# Controllers.net
KiCad netlist of a schematic drawn in Altium Designer
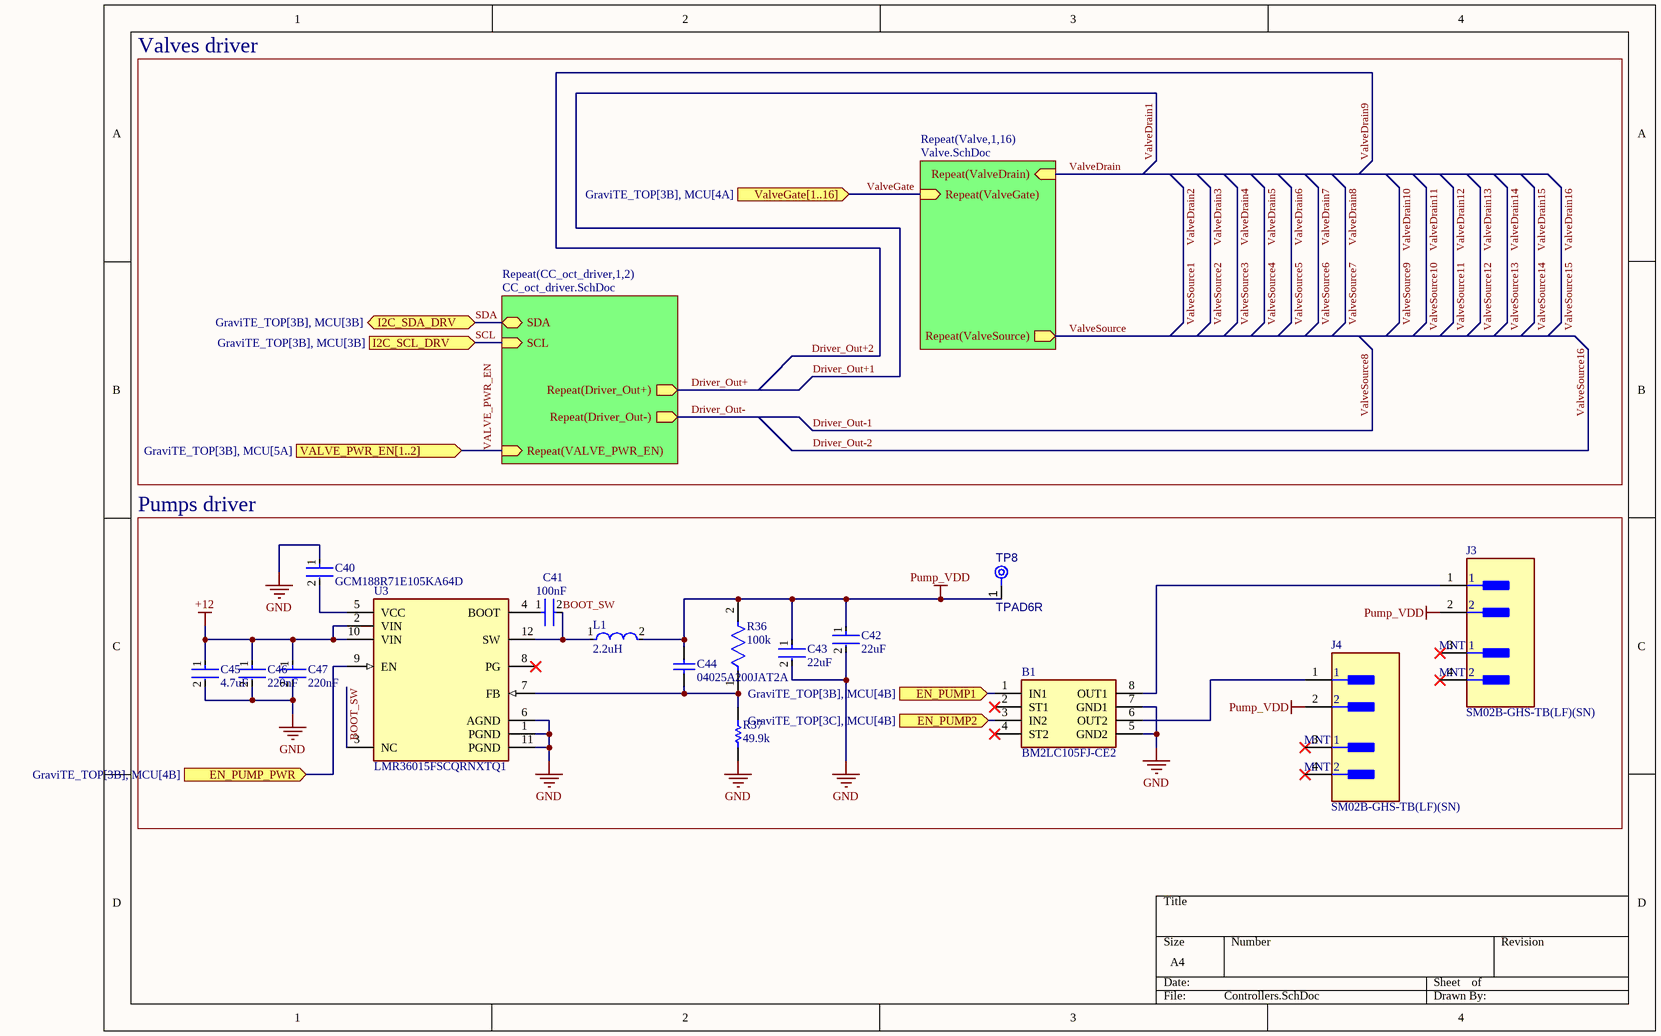
[diagram p0: Controllers.SchDoc]

(export (version "E")
  (design (tool "Eeschema 10.0.6"))
  (components
    (comp (ref "B1")
      (value "BM2LC105FJ-CE2")
      (footprint "SOIC127P600X165-8N")
      (description "Smart Low Side Switch ICs")
      (fields (field (name "MOUSER PART NUMBER") "755-BM2LC105FJ-CE2"))
      (libsource (lib "BM2LC105FJ-CE2") (part "BM2LC105FJ-CE2"))
    )
    (comp (ref "C40")
      (value "GCM188R71E105KA64D")
      (footprint "FP-GCM188-0_1-MFG")
      (fields (field (name "TOLERANCE") "10%") (field (name "VOLTAGE") "25V"))
      (libsource (lib "Altium Content Vault") (part "02cd4be3c70576c341d710602a673aa"))
    )
    (comp (ref "C41")
      (value "100nF")
      (footprint "FP-GCM155-0_05-IPC_C")
      (description "Ceramic Capacitor for Automotive 100nF ±10% 16VDC X7R 0402 Paper T/R")
      (fields (field (name "VOLTAGE") "16V") (field (name "TOLERANCE") "10%"))
      (libsource (lib "Altium Content Vault") (part "02cd4be3c70576c341d710602a673aa"))
    )
    (comp (ref "C42")
      (value "22uF")
      (footprint "FP-CGA5L-0_3-0_1-IPC_A")
      (description "Cap Ceramic 22uF 16V X5R 20% Pad SMD 1206 +85°C Automotive T/R")
      (fields (field (name "TOLERANCE") "20%"))
      (libsource (lib "Altium Content Vault") (part "b4654b650e69147ec39a6b967a45e02"))
    )
    (comp (ref "C43")
      (value "22uF")
      (footprint "FP-CGA5L-0_3-0_1-IPC_A")
      (description "Cap Ceramic 22uF 16V X5R 20% Pad SMD 1206 +85°C Automotive T/R")
      (fields (field (name "TOLERANCE") "20%"))
      (libsource (lib "Altium Content Vault") (part "b4654b650e69147ec39a6b967a45e02"))
    )
    (comp (ref "C44")
      (value "04025A200JAT2A")
      (footprint "CAPC1005X56X25NL10T15")
      (fields (field (name "MANUFACTURER") "AVX Interconnect / Elco"))
      (libsource (lib "Altium Content Vault") (part "CAP"))
    )
    (comp (ref "C45")
      (value "4.7uF")
      (footprint "FP-GCM21B-0_2-e0_2_0_7-IPC_B")
      (description "Ceramic Capacitor for Automotive 4.7uF ±10% 25VDC X7S 0805 Embossed T/R")
      (libsource (lib "Altium Content Vault") (part "11868f565c42a9108669ba33697ecf6"))
    )
    (comp (ref "C46")
      (value "220nF")
      (footprint "FP-GCM188-0_1-IPC_B")
      (description "Ceramic Capacitor for Automotive 220nF  ±10% 25VDC X7R 0603 Paper T/R")
      (fields (field (name "VOLTAGE") "25V") (field (name "TOLERANCE") "10%"))
      (libsource (lib "Altium Content Vault") (part "02cd4be3c70576c341d710602a673aa"))
    )
    (comp (ref "C47")
      (value "220nF")
      (footprint "FP-GCM188-0_1-IPC_B")
      (description "Ceramic Capacitor for Automotive 220nF  ±10% 25VDC X7R 0603 Paper T/R")
      (fields (field (name "VOLTAGE") "25V") (field (name "TOLERANCE") "10%"))
      (libsource (lib "Altium Content Vault") (part "02cd4be3c70576c341d710602a673aa"))
    )
    (comp (ref "J3")
      (value "SM02B-GHS-TB(LF)(SN)")
      (footprint "FP-SM02B-GHS-TB_LF_SN-MFG")
      (description "CONN HEADER SMD R/A 2POS 1.25MM")
      (libsource (lib "Altium Content Vault") (part "56ec3178a87b3978bdc1b3682cd516a"))
    )
    (comp (ref "J4")
      (value "SM02B-GHS-TB(LF)(SN)")
      (footprint "FP-SM02B-GHS-TB_LF_SN-MFG")
      (description "CONN HEADER SMD R/A 2POS 1.25MM")
      (libsource (lib "Altium Content Vault") (part "56ec3178a87b3978bdc1b3682cd516a"))
    )
    (comp (ref "L1")
      (value "2.2uH")
      (footprint "FP-MLP2520S-MFG")
      (description "Shielded Multilayer Inductor 2.2uH ±20% 1200mA 143mΩ SMD 1008")
      (fields (field (name "TOLERANCE") "20%"))
      (libsource (lib "Altium Content Vault") (part "725321dda6339637d4d059423bc1c3c"))
    )
    (comp (ref "R36")
      (value "100k")
      (footprint "FP-RMCF0402-IPC_C")
      (description "100kΩ ±1% 0.063W 0402 Thick Film Chip Resistor AEC-Q200 compliant")
      (fields (field (name "TOLERANCE") "1%"))
      (libsource (lib "Altium Content Vault") (part "1029c3af85768c4190bb7ad29bc67b5"))
    )
    (comp (ref "R37")
      (value "49.9k")
      (footprint "RESC1005X40X25LL05T05")
      (description "Chip Resistor, 49.9 KOhm, +/- 1%, 100 mW, -55 to 155 degC, 0402 (1005 Metric), RoHS, Tape and Reel")
      (fields (field (name "MANUFACTURER") "Basic Passives") (field (name "PARTNUMBER") "ERJ-2RKF4992X"))
      (libsource (lib "Altium Content Vault") (part "RES-2"))
    )
    (comp (ref "TP8")
      (value "TPAD6R")
      (footprint "TP06R")
      (description "0.6mm round")
      (libsource (lib "Piotr Słonka - priv") (part "CMP-001-0001-4"))
    )
    (comp (ref "U3")
      (value "LMR36015FSCQRNXTQ1")
      (footprint "FP-RNX0012B-MFG")
      (description "IC REG BUCK ADJ 1.5A 12VQFN")
      (libsource (lib "Altium Content Vault") (part "69d41d2a41b1d8294157df0305a048a"))
    )
  )
  (nets
    (net (code "19") (name "+12") (class "Default")
      (node (ref "C45") (pin "1") (pinfunction "1_1") (pintype "passive"))
      (node (ref "C46") (pin "1") (pinfunction "1_1") (pintype "passive"))
      (node (ref "C47") (pin "1") (pinfunction "1_1") (pintype "passive"))
      (node (ref "U3") (pin "10") (pinfunction "VIN_10") (pintype "power_in"))
      (node (ref "U3") (pin "2") (pinfunction "VIN_2") (pintype "power_in"))
    )
    (net (code "20") (name "/BOOT_SW") (class "Default")
      (node (ref "C41") (pin "2") (pinfunction "2_2") (pintype "passive"))
      (node (ref "L1") (pin "1") (pinfunction "1_1") (pintype "passive"))
      (node (ref "U3") (pin "12") (pinfunction "SW_12") (pintype "passive"))
      (node (ref "U3") (pin "3") (pinfunction "NC_3") (pintype "passive"))
    )
    (net (code "27") (name "/EN_PUMP1") (class "Default")
      (node (ref "B1") (pin "1") (pinfunction "IN1_1") (pintype "passive"))
    )
    (net (code "28") (name "/EN_PUMP2") (class "Default")
      (node (ref "B1") (pin "3") (pinfunction "IN2_3") (pintype "passive"))
    )
    (net (code "29") (name "/EN_PUMP_PWR") (class "Default")
      (node (ref "U3") (pin "9") (pinfunction "EN_9") (pintype "input"))
    )
    (net (code "52") (name "GND") (class "Default")
      (node (ref "B1") (pin "5") (pinfunction "GND2_5") (pintype "passive"))
      (node (ref "B1") (pin "7") (pinfunction "GND1_7") (pintype "passive"))
      (node (ref "C40") (pin "1") (pinfunction "1_1") (pintype "passive"))
      (node (ref "C42") (pin "2") (pinfunction "2_2") (pintype "passive"))
      (node (ref "C43") (pin "2") (pinfunction "2_2") (pintype "passive"))
      (node (ref "C45") (pin "2") (pinfunction "2_2") (pintype "passive"))
      (node (ref "C46") (pin "2") (pinfunction "2_2") (pintype "passive"))
      (node (ref "C47") (pin "2") (pinfunction "2_2") (pintype "passive"))
      (node (ref "R37") (pin "1") (pinfunction "1_1") (pintype "passive"))
      (node (ref "U3") (pin "1") (pinfunction "PGND_1") (pintype "power_in"))
      (node (ref "U3") (pin "11") (pinfunction "PGND_11") (pintype "power_in"))
      (node (ref "U3") (pin "6") (pinfunction "AGND_6") (pintype "power_in"))
    )
    (net (code "53") (name "Net-(B1-OUT1)") (class "Default")
      (node (ref "B1") (pin "8") (pinfunction "OUT1_8") (pintype "passive"))
      (node (ref "J3") (pin "1") (pinfunction "1_1") (pintype "passive"))
    )
    (net (code "54") (name "Net-(B1-OUT2)") (class "Default")
      (node (ref "B1") (pin "6") (pinfunction "OUT2_6") (pintype "passive"))
      (node (ref "J4") (pin "1") (pinfunction "1_1") (pintype "passive"))
    )
    (net (code "55") (name "Net-(U3-BOOT)") (class "Default")
      (node (ref "C41") (pin "1") (pinfunction "1_1") (pintype "passive"))
      (node (ref "U3") (pin "4") (pinfunction "BOOT_4") (pintype "passive"))
    )
    (net (code "56") (name "Net-(U3-FB)") (class "Default")
      (node (ref "C44") (pin "1") (pinfunction "1_1") (pintype "passive"))
      (node (ref "R36") (pin "1") (pinfunction "1_1") (pintype "passive"))
      (node (ref "R37") (pin "2") (pinfunction "2_2") (pintype "passive"))
      (node (ref "U3") (pin "7") (pinfunction "FB_7") (pintype "input"))
    )
    (net (code "57") (name "Net-(U3-VCC)") (class "Default")
      (node (ref "C40") (pin "2") (pinfunction "2_2") (pintype "passive"))
      (node (ref "U3") (pin "5") (pinfunction "VCC_5") (pintype "power_in"))
    )
    (net (code "58") (name "Pump_VDD") (class "Default")
      (node (ref "C42") (pin "1") (pinfunction "1_1") (pintype "passive"))
      (node (ref "C43") (pin "1") (pinfunction "1_1") (pintype "passive"))
      (node (ref "C44") (pin "2") (pinfunction "2_2") (pintype "passive"))
      (node (ref "J3") (pin "2") (pinfunction "2_2") (pintype "passive"))
      (node (ref "J4") (pin "2") (pinfunction "2_2") (pintype "passive"))
      (node (ref "L1") (pin "2") (pinfunction "2_2") (pintype "passive"))
      (node (ref "R36") (pin "2") (pinfunction "2_2") (pintype "passive"))
      (node (ref "TP8") (pin "1") (pinfunction "TP_1") (pintype "passive"))
    )
    (net (code "59") (name "unconnected-(B1-ST1-Pad2)") (class "Default")
      (node (ref "B1") (pin "2") (pinfunction "ST1_2") (pintype "passive+no_connect"))
    )
    (net (code "60") (name "unconnected-(B1-ST2-Pad4)") (class "Default")
      (node (ref "B1") (pin "4") (pinfunction "ST2_4") (pintype "passive+no_connect"))
    )
    (net (code "61") (name "unconnected-(J3-MNT_1-Pad3)") (class "Default")
      (node (ref "J3") (pin "3") (pinfunction "MNT_1_3") (pintype "passive+no_connect"))
    )
    (net (code "62") (name "unconnected-(J3-MNT_2-Pad4)") (class "Default")
      (node (ref "J3") (pin "4") (pinfunction "MNT_2_4") (pintype "passive+no_connect"))
    )
    (net (code "63") (name "unconnected-(J4-MNT_1-Pad3)") (class "Default")
      (node (ref "J4") (pin "3") (pinfunction "MNT_1_3") (pintype "passive+no_connect"))
    )
    (net (code "64") (name "unconnected-(J4-MNT_2-Pad4)") (class "Default")
      (node (ref "J4") (pin "4") (pinfunction "MNT_2_4") (pintype "passive+no_connect"))
    )
    (net (code "65") (name "unconnected-(U3-PG-Pad8)") (class "Default")
      (node (ref "U3") (pin "8") (pinfunction "PG_8") (pintype "open_collector+no_connect"))
    )
  )
)
